# TPDH-Walrus_HardMount.net
KiCad netlist of a schematic drawn in EAGLE
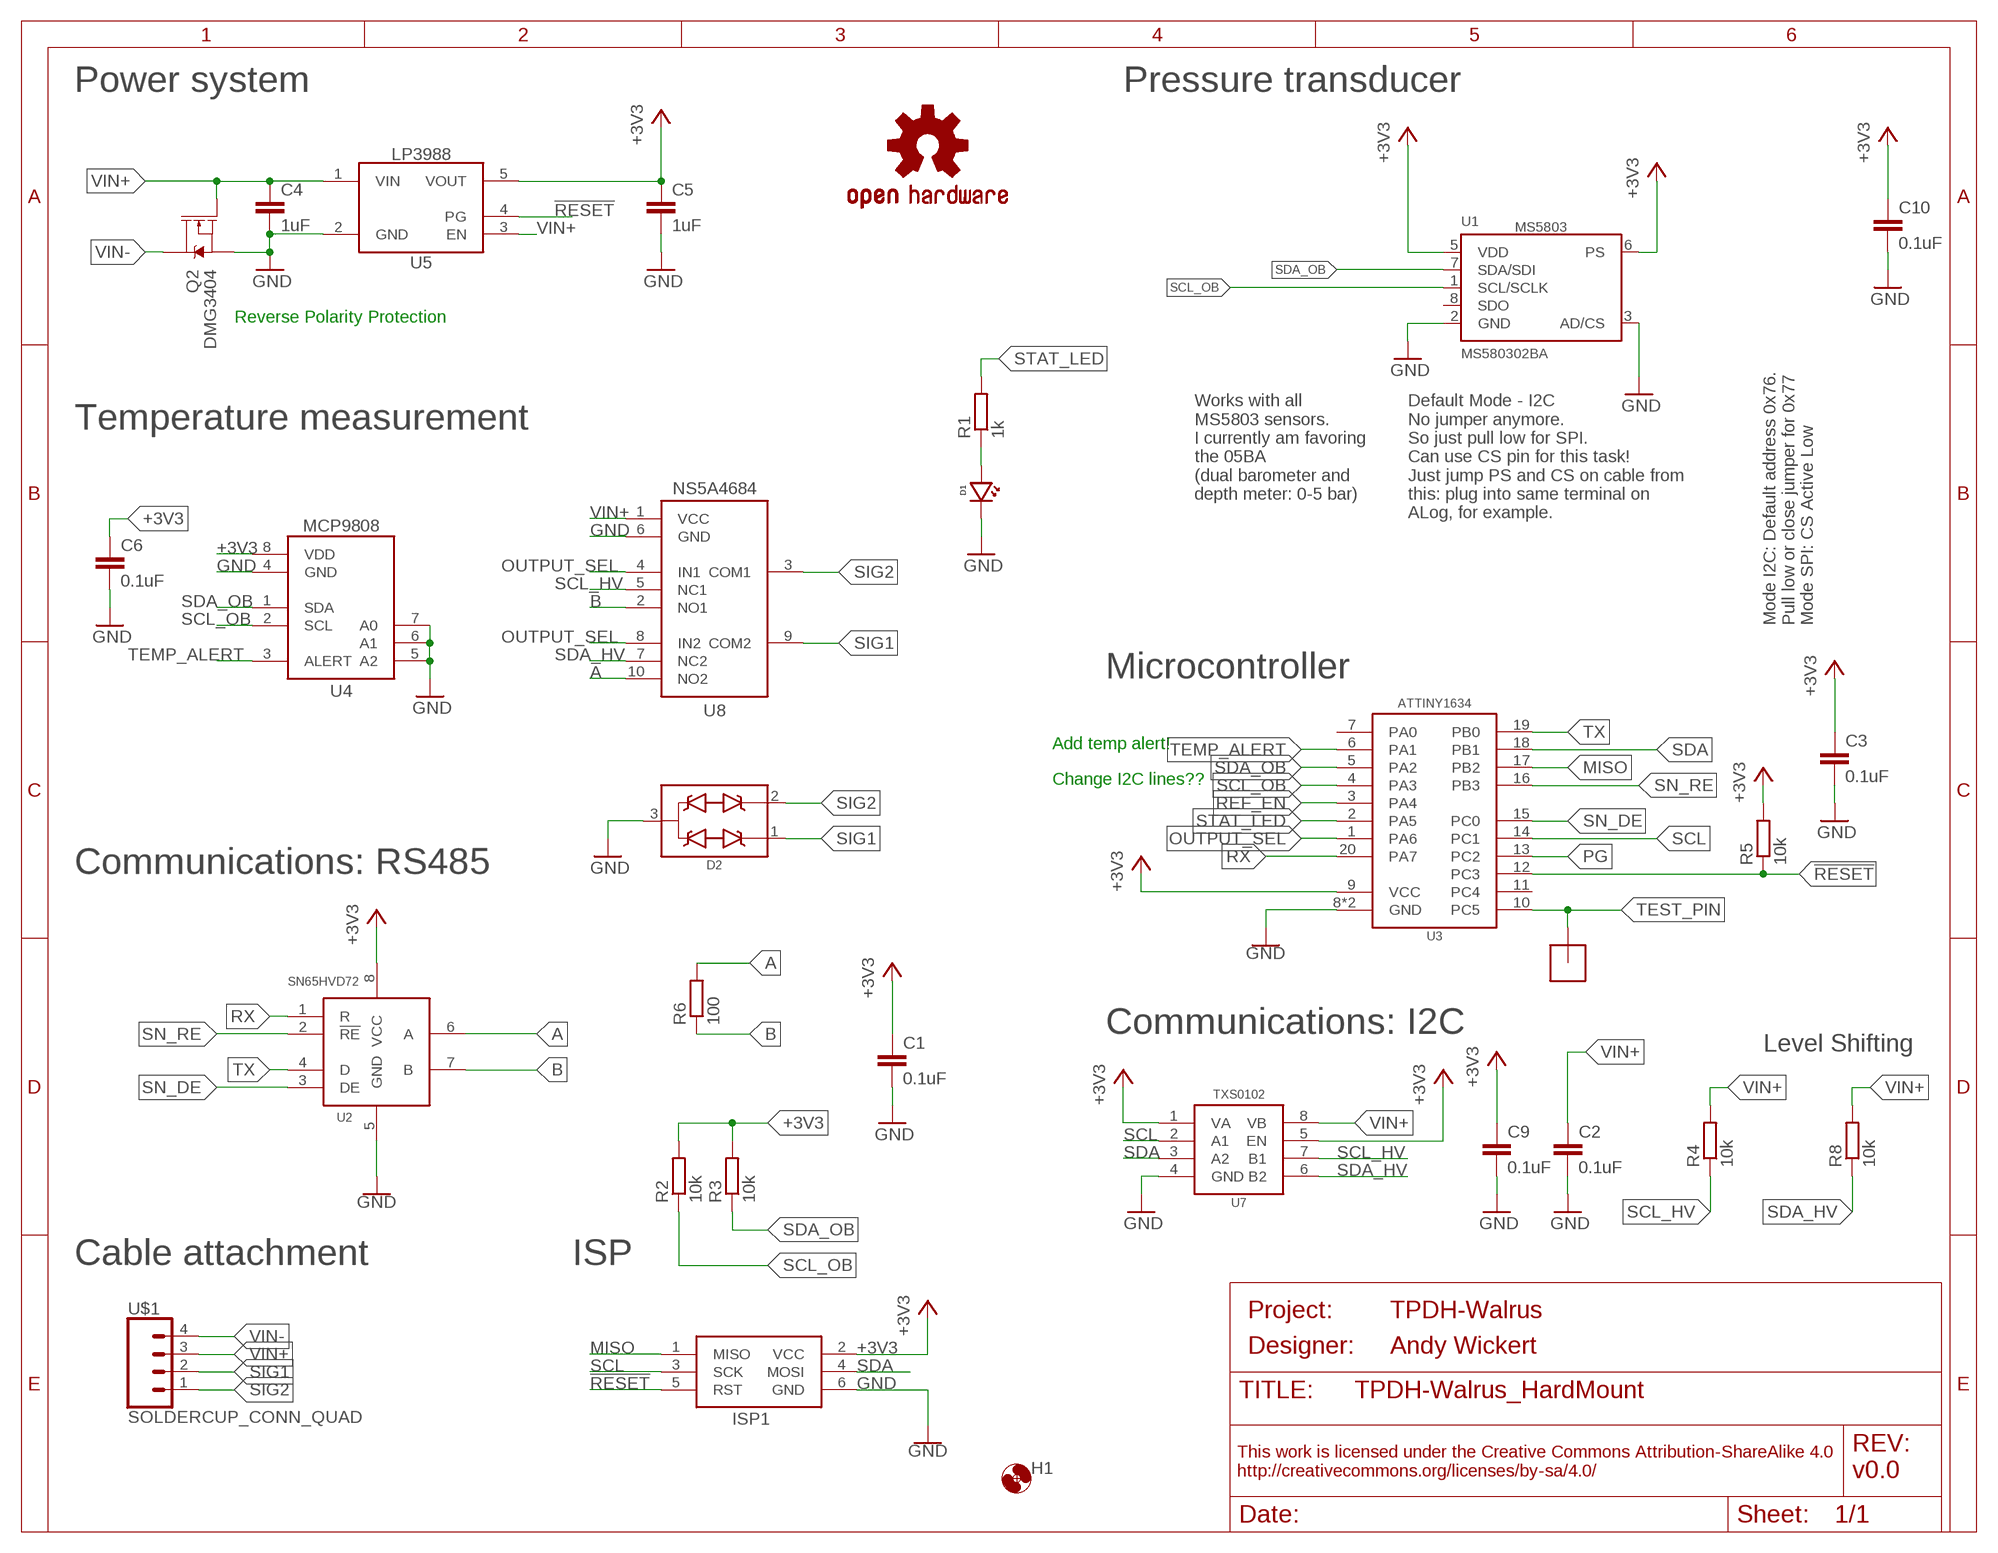
[diagram p0: schematic, sheet 1]

(export (version "E")
  (design (tool "Eeschema 10.0.6"))
  (components
    (comp (ref "C1")
      (value "0.1uF")
      (footprint "eagle-import:C0402")
      (fields (field (name "MF") "Murata") (field (name "MPN") "GCM155R71C104KA55D"))
      (libsource (lib "eagle-import") (part "C-EUC04020.1UF"))
    )
    (comp (ref "C2")
      (value "0.1uF")
      (footprint "eagle-import:C0402")
      (fields (field (name "MF") "Murata") (field (name "MPN") "GCM155R71C104KA55D"))
      (libsource (lib "eagle-import") (part "C-EUC04020.1UF"))
    )
    (comp (ref "C3")
      (value "0.1uF")
      (footprint "eagle-import:C0402")
      (fields (field (name "MF") "Murata") (field (name "MPN") "GCM155R71C104KA55D"))
      (libsource (lib "eagle-import") (part "C-EUC04020.1UF"))
    )
    (comp (ref "C4")
      (value "1uF")
      (footprint "eagle-import:C0603")
      (fields (field (name "MF") "Samsung") (field (name "MPN") "1276-6524-1-ND"))
      (libsource (lib "eagle-import") (part "C-EUC06031UF"))
    )
    (comp (ref "C5")
      (value "1uF")
      (footprint "eagle-import:C0603")
      (fields (field (name "MF") "Samsung") (field (name "MPN") "1276-6524-1-ND"))
      (libsource (lib "eagle-import") (part "C-EUC06031UF"))
    )
    (comp (ref "C6")
      (value "0.1uF")
      (footprint "eagle-import:C0402")
      (fields (field (name "MF") "Murata") (field (name "MPN") "GCM155R71C104KA55D"))
      (libsource (lib "eagle-import") (part "C-EUC04020.1UF"))
    )
    (comp (ref "C9")
      (value "0.1uF")
      (footprint "eagle-import:C0402")
      (fields (field (name "MF") "Murata") (field (name "MPN") "GCM155R71C104KA55D"))
      (libsource (lib "eagle-import") (part "C-EUC04020.1UF"))
    )
    (comp (ref "C10")
      (value "0.1uF")
      (footprint "eagle-import:C0402")
      (fields (field (name "MF") "Murata") (field (name "MPN") "GCM155R71C104KA55D"))
      (libsource (lib "eagle-import") (part "C-EUC04020.1UF"))
    )
    (comp (ref "D1")
      (value "LEDBLUE0603")
      (footprint "eagle-import:LED_0603")
      (fields (field (name "MF") "Wurth") (field (name "MPN") "150060BS75000"))
      (libsource (lib "eagle-import") (part "LED0603BLUE"))
    )
    (comp (ref "D2")
      (value "TVSSM712")
      (footprint "eagle-import:SOT23-3")
      (fields (field (name "MF") "Bourns") (field (name "MPN") "CDSOT23-SM712"))
      (libsource (lib "eagle-import") (part "TVSSM712"))
    )
    (comp (ref "H1")
      (value "MOUNTING_HOLE2_NP")
      (footprint "eagle-import:2_56")
      (fields (field (name "MPN") "DNP"))
      (libsource (lib "eagle-import") (part "MOUNTING_HOLE2_NP"))
    )
    (comp (ref "ISP1")
      (value "AVRISP-6")
      (footprint "eagle-import:AVRISP")
      (libsource (lib "eagle-import") (part "AVRISP-6"))
    )
    (comp (ref "LOGO1")
      (value "OSHW-LOGOM")
      (footprint "eagle-import:OSHW-LOGO-M")
      (fields (field (name "MPN") "DNP"))
      (libsource (lib "eagle-import") (part "OSHW-LOGOM"))
    )
    (comp (ref "Q2")
      (value "DMG3404")
      (footprint "eagle-import:SOT23-3")
      (fields (field (name "MF") "Diodes Incorporated") (field (name "MPN") "DMG3404L-7"))
      (libsource (lib "eagle-import") (part "MOSFET-NCH-DMG3404L"))
    )
    (comp (ref "R1")
      (value "1k")
      (footprint "eagle-import:R0603")
      (fields (field (name "MF") "Yageo") (field (name "MPN") "AC0603FR-071KL"))
      (libsource (lib "eagle-import") (part "R-EU_R06031K"))
    )
    (comp (ref "R2")
      (value "10k")
      (footprint "eagle-import:R0402")
      (fields (field (name "MF") "Yageo") (field (name "MPN") "RC0402FR-0710KL"))
      (libsource (lib "eagle-import") (part "R-EU_R040210K"))
    )
    (comp (ref "R3")
      (value "10k")
      (footprint "eagle-import:R0402")
      (fields (field (name "MF") "Yageo") (field (name "MPN") "RC0402FR-0710KL"))
      (libsource (lib "eagle-import") (part "R-EU_R040210K"))
    )
    (comp (ref "R4")
      (value "10k")
      (footprint "eagle-import:R0402")
      (fields (field (name "MF") "Yageo") (field (name "MPN") "RC0402FR-0710KL"))
      (libsource (lib "eagle-import") (part "R-EU_R040210K"))
    )
    (comp (ref "R5")
      (value "10k")
      (footprint "eagle-import:R0402")
      (fields (field (name "MF") "Yageo") (field (name "MPN") "RC0402FR-0710KL"))
      (libsource (lib "eagle-import") (part "R-EU_R040210K"))
    )
    (comp (ref "R6")
      (value "100")
      (footprint "eagle-import:R0402")
      (fields (field (name "MF") "Yageo") (field (name "MPN") "RC0402FR-07100RL"))
      (libsource (lib "eagle-import") (part "R-EU_R0402100"))
    )
    (comp (ref "R8")
      (value "10k")
      (footprint "eagle-import:R0402")
      (fields (field (name "MF") "Yageo") (field (name "MPN") "RC0402FR-0710KL"))
      (libsource (lib "eagle-import") (part "R-EU_R040210K"))
    )
    (comp (ref "U$1")
      (value "SOLDERCUP_CONN_QUAD")
      (footprint "eagle-import:SOLDERCUP_CONN_QUAD")
      (fields (field (name "MF") "TE Connectivity") (field (name "MPN") "1838893-2"))
      (libsource (lib "eagle-import") (part "SOLDERCUP_CONN_QUAD"))
    )
    (comp (ref "U$12")
      (value "POGO_PAD")
      (footprint "eagle-import:POGO_PAD")
      (fields (field (name "MPN") "DNP"))
      (libsource (lib "eagle-import") (part "POGO_PAD"))
    )
    (comp (ref "U1")
      (value "MS580302BA")
      (footprint "eagle-import:MS5803")
      (fields (field (name "MF") "TE Connectivity") (field (name "MPN") "MS580302BA01-00"))
      (libsource (lib "eagle-import") (part "MS580302BA"))
    )
    (comp (ref "U2")
      (value "SN65HVD72DSOIC")
      (footprint "eagle-import:SO08")
      (fields (field (name "DISP") "SN65HVD72") (field (name "MF") "TI") (field (name "MPN") "SN65HVD72DR"))
      (libsource (lib "eagle-import") (part "SN65HVD72SOICD"))
    )
    (comp (ref "U3")
      (value "ATTINY1634QFN")
      (footprint "eagle-import:QFN20")
      (fields (field (name "MF") "Atmel") (field (name "MPN") "ATTINY1634-MUR"))
      (libsource (lib "eagle-import") (part "ATTINY1634QFN"))
    )
    (comp (ref "U4")
      (value "MCP9808MSOP")
      (footprint "eagle-import:MSOP_8")
      (fields (field (name "MF") "Microchip") (field (name "MPN") "MCP9808T-E/MS"))
      (libsource (lib "eagle-import") (part "MCP9808MSOP"))
    )
    (comp (ref "U5")
      (value "LP39883.3VDBV")
      (footprint "eagle-import:DBV0005A")
      (fields (field (name "MF") "TI") (field (name "MPN") "LP3988IMF-3.3/NOPB"))
      (libsource (lib "eagle-import") (part "LP3988DBV3.3V"))
    )
    (comp (ref "U7")
      (value "TXS0102DQM")
      (footprint "eagle-import:DQM_R-PX2SON-N8")
      (fields (field (name "MF") "TI") (field (name "MPN") "TXS0102DQMR"))
      (libsource (lib "eagle-import") (part "TXS0102DQM"))
    )
    (comp (ref "U8")
      (value "NS5A4684S")
      (footprint "eagle-import:WQFN10")
      (fields
        (field (name "DISP") "NS5A4684")
        (field (name "MF") "ON Semiconductor")
        (field (name "MPN") "NS5A4684SMNTAG")
      )
      (libsource (lib "eagle-import") (part "NS5A4684S"))
    )
  )
  (nets
    (net (code "1") (name "+3V3") (class "Default")
      (node (ref "C1") (pin "1") (pinfunction "1_1") (pintype "passive"))
      (node (ref "C10") (pin "1") (pinfunction "1_1") (pintype "passive"))
      (node (ref "C3") (pin "1") (pinfunction "1_1") (pintype "passive"))
      (node (ref "C5") (pin "1") (pinfunction "1_1") (pintype "passive"))
      (node (ref "C6") (pin "1") (pinfunction "1_1") (pintype "passive"))
      (node (ref "C9") (pin "1") (pinfunction "1_1") (pintype "passive"))
      (node (ref "ISP1") (pin "2") (pinfunction "VCC_2") (pintype "power_in"))
      (node (ref "R2") (pin "2") (pinfunction "2_2") (pintype "passive"))
      (node (ref "R3") (pin "2") (pinfunction "2_2") (pintype "passive"))
      (node (ref "R5") (pin "2") (pinfunction "2_2") (pintype "passive"))
      (node (ref "U1") (pin "5") (pinfunction "VDD_5") (pintype "power_in"))
      (node (ref "U1") (pin "6") (pinfunction "PS_6") (pintype "input"))
      (node (ref "U2") (pin "8") (pinfunction "VCC_8") (pintype "power_in"))
      (node (ref "U3") (pin "9") (pinfunction "VCC_9") (pintype "power_in"))
      (node (ref "U4") (pin "8") (pinfunction "VDD_8") (pintype "power_in"))
      (node (ref "U5") (pin "5") (pinfunction "VOUT_5") (pintype "power_in"))
      (node (ref "U7") (pin "1") (pinfunction "VA_1") (pintype "power_in"))
      (node (ref "U7") (pin "5") (pinfunction "EN_5") (pintype "input"))
    )
    (net (code "2") (name "/~{RESET}") (class "Default")
      (node (ref "ISP1") (pin "5") (pinfunction "RST_5") (pintype "output"))
      (node (ref "R5") (pin "1") (pinfunction "1_1") (pintype "passive"))
      (node (ref "U3") (pin "12") (pinfunction "PC3_12") (pintype "bidirectional"))
      (node (ref "U5") (pin "4") (pinfunction "PG_4") (pintype "output"))
    )
    (net (code "3") (name "A") (class "Default")
      (node (ref "R6") (pin "2") (pinfunction "2_2") (pintype "passive"))
      (node (ref "U2") (pin "6") (pinfunction "A_6") (pintype "bidirectional"))
      (node (ref "U8") (pin "10") (pinfunction "NO2_10") (pintype "bidirectional"))
    )
    (net (code "4") (name "B") (class "Default")
      (node (ref "R6") (pin "1") (pinfunction "1_1") (pintype "passive"))
      (node (ref "U2") (pin "7") (pinfunction "B_7") (pintype "bidirectional"))
      (node (ref "U8") (pin "2") (pinfunction "NO1_2") (pintype "bidirectional"))
    )
    (net (code "5") (name "GND") (class "Default")
      (node (ref "C1") (pin "2") (pinfunction "2_2") (pintype "passive"))
      (node (ref "C10") (pin "2") (pinfunction "2_2") (pintype "passive"))
      (node (ref "C2") (pin "2") (pinfunction "2_2") (pintype "passive"))
      (node (ref "C3") (pin "2") (pinfunction "2_2") (pintype "passive"))
      (node (ref "C4") (pin "2") (pinfunction "2_2") (pintype "passive"))
      (node (ref "C5") (pin "2") (pinfunction "2_2") (pintype "passive"))
      (node (ref "C6") (pin "2") (pinfunction "2_2") (pintype "passive"))
      (node (ref "C9") (pin "2") (pinfunction "2_2") (pintype "passive"))
      (node (ref "D1") (pin "CATHODE") (pinfunction "CATHODE_CATHODE") (pintype "power_in"))
      (node (ref "D2") (pin "3") (pinfunction "COM_3") (pintype "input"))
      (node (ref "ISP1") (pin "6") (pinfunction "GND_6") (pintype "power_in"))
      (node (ref "Q2") (pin "2") (pinfunction "S_2") (pintype "bidirectional"))
      (node (ref "U1") (pin "2") (pinfunction "GND_2") (pintype "power_in"))
      (node (ref "U1") (pin "3") (pinfunction "AD/CS_3") (pintype "input"))
      (node (ref "U2") (pin "5") (pinfunction "GND_5") (pintype "power_in"))
      (node (ref "U3") (pin "8") (pinfunction "GND_8") (pintype "power_in"))
      (node (ref "U3") (pin "EP") (pinfunction "GND_EP") (pintype "power_in"))
      (node (ref "U4") (pin "4") (pinfunction "GND_4") (pintype "power_in"))
      (node (ref "U4") (pin "5") (pinfunction "A2_5") (pintype "input"))
      (node (ref "U4") (pin "6") (pinfunction "A1_6") (pintype "input"))
      (node (ref "U4") (pin "7") (pinfunction "A0_7") (pintype "input"))
      (node (ref "U5") (pin "2") (pinfunction "GND_2") (pintype "power_in"))
      (node (ref "U7") (pin "4") (pinfunction "GND_4") (pintype "power_in"))
      (node (ref "U8") (pin "6") (pinfunction "GND_6") (pintype "power_in"))
    )
    (net (code "6") (name "MISO") (class "Default")
      (node (ref "ISP1") (pin "1") (pinfunction "MISO_1") (pintype "input"))
      (node (ref "U3") (pin "17") (pinfunction "PB2_17") (pintype "bidirectional"))
    )
    (net (code "7") (name "Net-(D1-PadANODE)") (class "Default")
      (node (ref "D1") (pin "ANODE") (pinfunction "ANODE_ANODE") (pintype "power_in"))
      (node (ref "R1") (pin "1") (pinfunction "1_1") (pintype "passive"))
    )
    (net (code "8") (name "OUTPUT_SEL") (class "Default")
      (node (ref "U3") (pin "1") (pinfunction "PA6_1") (pintype "bidirectional"))
      (node (ref "U8") (pin "4") (pinfunction "IN1_4") (pintype "input"))
      (node (ref "U8") (pin "8") (pinfunction "IN2_8") (pintype "input"))
    )
    (net (code "9") (name "PG") (class "Default")
      (node (ref "U3") (pin "13") (pinfunction "PC2_13") (pintype "bidirectional"))
    )
    (net (code "10") (name "REF_EN") (class "Default")
      (node (ref "U3") (pin "3") (pinfunction "PA4_3") (pintype "bidirectional"))
    )
    (net (code "11") (name "RX") (class "Default")
      (node (ref "U2") (pin "1") (pinfunction "R_1") (pintype "output"))
      (node (ref "U3") (pin "20") (pinfunction "PA7_20") (pintype "bidirectional"))
    )
    (net (code "12") (name "SCL") (class "Default")
      (node (ref "ISP1") (pin "3") (pinfunction "SCK_3") (pintype "output"))
      (node (ref "U3") (pin "14") (pinfunction "PC1_14") (pintype "bidirectional"))
      (node (ref "U7") (pin "2") (pinfunction "A1_2") (pintype "bidirectional"))
    )
    (net (code "13") (name "SCL_HV") (class "Default")
      (node (ref "R4") (pin "1") (pinfunction "1_1") (pintype "passive"))
      (node (ref "U7") (pin "7") (pinfunction "B1_7") (pintype "bidirectional"))
      (node (ref "U8") (pin "5") (pinfunction "NC1_5") (pintype "bidirectional"))
    )
    (net (code "14") (name "SCL_OB") (class "Default")
      (node (ref "R2") (pin "1") (pinfunction "1_1") (pintype "passive"))
      (node (ref "U1") (pin "1") (pinfunction "SCL/SCLK_1") (pintype "input"))
      (node (ref "U3") (pin "4") (pinfunction "PA3_4") (pintype "bidirectional"))
      (node (ref "U4") (pin "2") (pinfunction "SCL_2") (pintype "input"))
    )
    (net (code "15") (name "SDA") (class "Default")
      (node (ref "ISP1") (pin "4") (pinfunction "MOSI_4") (pintype "output"))
      (node (ref "U3") (pin "18") (pinfunction "PB1_18") (pintype "bidirectional"))
      (node (ref "U7") (pin "3") (pinfunction "A2_3") (pintype "bidirectional"))
    )
    (net (code "16") (name "SDA_HV") (class "Default")
      (node (ref "R8") (pin "1") (pinfunction "1_1") (pintype "passive"))
      (node (ref "U7") (pin "6") (pinfunction "B2_6") (pintype "bidirectional"))
      (node (ref "U8") (pin "7") (pinfunction "NC2_7") (pintype "bidirectional"))
    )
    (net (code "17") (name "SDA_OB") (class "Default")
      (node (ref "R3") (pin "1") (pinfunction "1_1") (pintype "passive"))
      (node (ref "U1") (pin "7") (pinfunction "SDA/SDI_7") (pintype "bidirectional"))
      (node (ref "U3") (pin "5") (pinfunction "PA2_5") (pintype "bidirectional"))
      (node (ref "U4") (pin "1") (pinfunction "SDA_1") (pintype "bidirectional"))
    )
    (net (code "18") (name "SIG1") (class "Default")
      (node (ref "D2") (pin "1") (pinfunction "D1_1") (pintype "input"))
      (node (ref "U$1") (pin "2") (pinfunction "2_2") (pintype "passive"))
      (node (ref "U8") (pin "9") (pinfunction "COM2_9") (pintype "bidirectional"))
    )
    (net (code "19") (name "SIG2") (class "Default")
      (node (ref "D2") (pin "2") (pinfunction "D2_2") (pintype "input"))
      (node (ref "U$1") (pin "1") (pinfunction "1_1") (pintype "passive"))
      (node (ref "U8") (pin "3") (pinfunction "COM1_3") (pintype "bidirectional"))
    )
    (net (code "20") (name "SN_DE") (class "Default")
      (node (ref "U2") (pin "3") (pinfunction "DE_3") (pintype "input"))
      (node (ref "U3") (pin "15") (pinfunction "PC0_15") (pintype "bidirectional"))
    )
    (net (code "21") (name "SN_RE") (class "Default")
      (node (ref "U2") (pin "2") (pinfunction "~{RE}_2") (pintype "input"))
      (node (ref "U3") (pin "16") (pinfunction "PB3_16") (pintype "bidirectional"))
    )
    (net (code "22") (name "STAT_LED") (class "Default")
      (node (ref "R1") (pin "2") (pinfunction "2_2") (pintype "passive"))
      (node (ref "U3") (pin "2") (pinfunction "PA5_2") (pintype "bidirectional"))
    )
    (net (code "23") (name "TEMP_ALERT") (class "Default")
      (node (ref "U3") (pin "6") (pinfunction "PA1_6") (pintype "bidirectional"))
      (node (ref "U4") (pin "3") (pinfunction "ALERT_3") (pintype "output"))
    )
    (net (code "24") (name "TEST_PIN") (class "Default")
      (node (ref "U$12") (pin "P$1") (pinfunction "P$1_P$1") (pintype "bidirectional"))
      (node (ref "U3") (pin "10") (pinfunction "PC5_10") (pintype "bidirectional"))
    )
    (net (code "25") (name "TX") (class "Default")
      (node (ref "U2") (pin "4") (pinfunction "D_4") (pintype "input"))
      (node (ref "U3") (pin "19") (pinfunction "PB0_19") (pintype "bidirectional"))
    )
    (net (code "26") (name "VIN+") (class "Default")
      (node (ref "C2") (pin "1") (pinfunction "1_1") (pintype "passive"))
      (node (ref "C4") (pin "1") (pinfunction "1_1") (pintype "passive"))
      (node (ref "Q2") (pin "1") (pinfunction "G_1") (pintype "bidirectional"))
      (node (ref "R4") (pin "2") (pinfunction "2_2") (pintype "passive"))
      (node (ref "R8") (pin "2") (pinfunction "2_2") (pintype "passive"))
      (node (ref "U$1") (pin "3") (pinfunction "3_3") (pintype "passive"))
      (node (ref "U5") (pin "1") (pinfunction "VIN_1") (pintype "power_in"))
      (node (ref "U5") (pin "3") (pinfunction "EN_3") (pintype "input"))
      (node (ref "U7") (pin "8") (pinfunction "VB_8") (pintype "power_in"))
      (node (ref "U8") (pin "1") (pinfunction "VCC_1") (pintype "power_in"))
    )
    (net (code "27") (name "VIN-") (class "Default")
      (node (ref "Q2") (pin "3") (pinfunction "D_3") (pintype "bidirectional"))
      (node (ref "U$1") (pin "4") (pinfunction "4_4") (pintype "passive"))
    )
    (net (code "28") (name "unconnected-(U1-SDO-Pad8)") (class "Default")
      (node (ref "U1") (pin "8") (pinfunction "SDO_8") (pintype "output"))
    )
    (net (code "29") (name "unconnected-(U3-PA0-Pad7)") (class "Default")
      (node (ref "U3") (pin "7") (pinfunction "PA0_7") (pintype "bidirectional"))
    )
    (net (code "30") (name "unconnected-(U3-PC4-Pad11)") (class "Default")
      (node (ref "U3") (pin "11") (pinfunction "PC4_11") (pintype "bidirectional"))
    )
  )
)
